# wav_player_861_mosfet_5x5.net
KiCad netlist of a schematic drawn in EAGLE
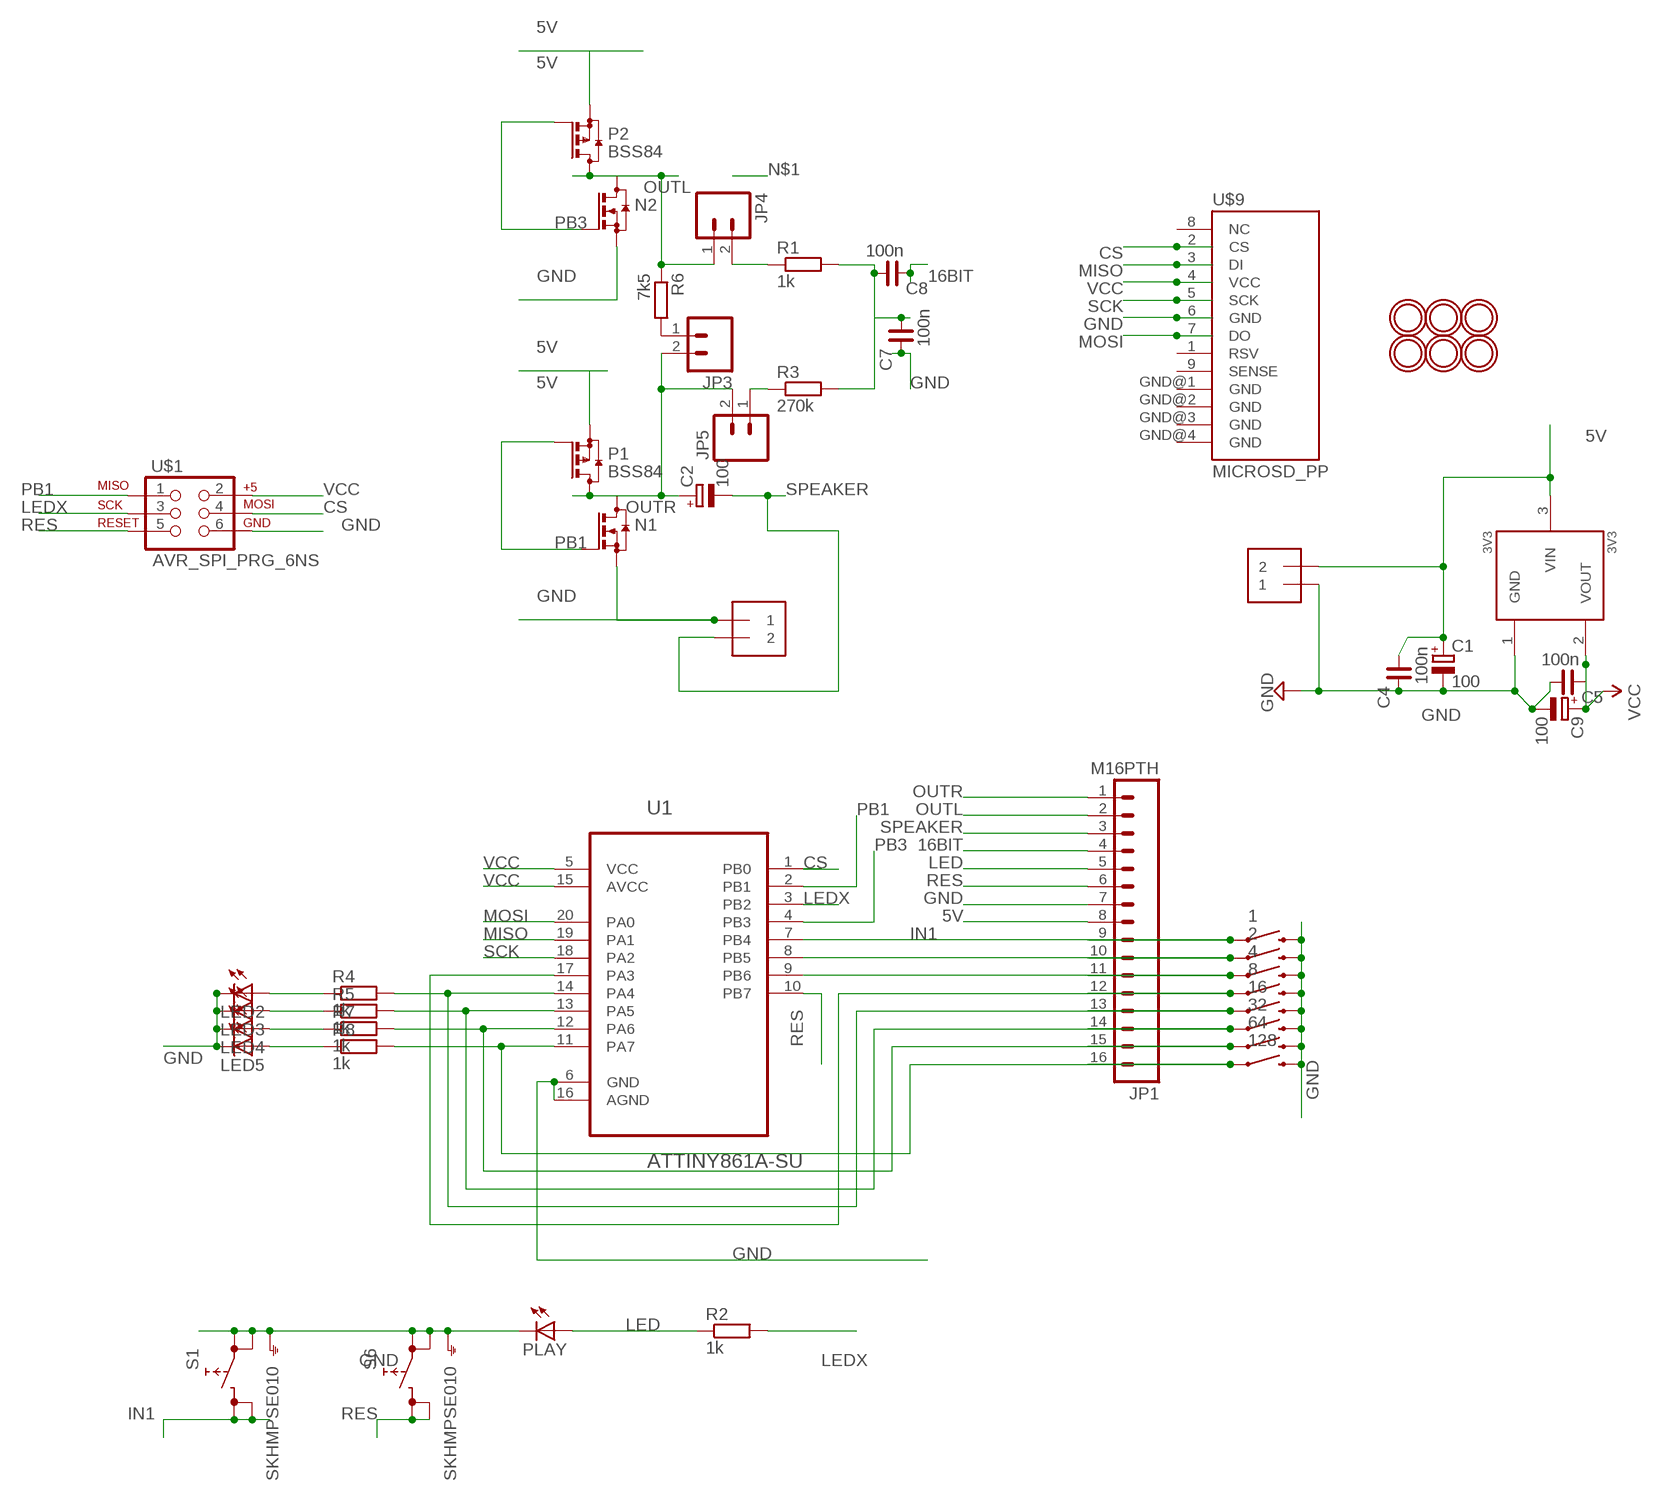
[diagram p0: schematic, sheet 1]

(export (version "E")
  (design (tool "Eeschema 10.0.6"))
  (components
    (comp (ref "1")
      (value "SWITCH-MOMENTARY-2-SMD-1101NE")
      (footprint "eagle-import:TACTILE-SWITCH-1101NE")
      (libsource (lib "eagle-import") (part "SWITCH-MOMENTARY-2-SMD-1101NE"))
    )
    (comp (ref "2")
      (value "SWITCH-MOMENTARY-2-SMD-1101NE")
      (footprint "eagle-import:TACTILE-SWITCH-1101NE")
      (libsource (lib "eagle-import") (part "SWITCH-MOMENTARY-2-SMD-1101NE"))
    )
    (comp (ref "3V3")
      (value "3V3")
      (footprint "eagle-import:SOT23")
      (libsource (lib "eagle-import") (part "MCP1700T"))
    )
    (comp (ref "4")
      (value "SWITCH-MOMENTARY-2-SMD-1101NE")
      (footprint "eagle-import:TACTILE-SWITCH-1101NE")
      (libsource (lib "eagle-import") (part "SWITCH-MOMENTARY-2-SMD-1101NE"))
    )
    (comp (ref "8")
      (value "SWITCH-MOMENTARY-2-SMD-1101NE")
      (footprint "eagle-import:TACTILE-SWITCH-1101NE")
      (libsource (lib "eagle-import") (part "SWITCH-MOMENTARY-2-SMD-1101NE"))
    )
    (comp (ref "16")
      (value "SWITCH-MOMENTARY-2-SMD-1101NE")
      (footprint "eagle-import:TACTILE-SWITCH-1101NE")
      (libsource (lib "eagle-import") (part "SWITCH-MOMENTARY-2-SMD-1101NE"))
    )
    (comp (ref "32")
      (value "SWITCH-MOMENTARY-2-SMD-1101NE")
      (footprint "eagle-import:TACTILE-SWITCH-1101NE")
      (libsource (lib "eagle-import") (part "SWITCH-MOMENTARY-2-SMD-1101NE"))
    )
    (comp (ref "64")
      (value "SWITCH-MOMENTARY-2-SMD-1101NE")
      (footprint "eagle-import:TACTILE-SWITCH-1101NE")
      (libsource (lib "eagle-import") (part "SWITCH-MOMENTARY-2-SMD-1101NE"))
    )
    (comp (ref "128")
      (value "SWITCH-MOMENTARY-2-SMD-1101NE")
      (footprint "eagle-import:TACTILE-SWITCH-1101NE")
      (libsource (lib "eagle-import") (part "SWITCH-MOMENTARY-2-SMD-1101NE"))
    )
    (comp (ref "C1")
      (value "100")
      (footprint "eagle-import:153CLV-0605")
      (libsource (lib "eagle-import") (part "CPOL-EU153CLV-0605"))
    )
    (comp (ref "C2")
      (value "100")
      (footprint "eagle-import:153CLV-0605")
      (libsource (lib "eagle-import") (part "CPOL-EU153CLV-0605"))
    )
    (comp (ref "C4")
      (value "100n")
      (footprint "eagle-import:C0603")
      (libsource (lib "eagle-import") (part "C_0603"))
    )
    (comp (ref "C5")
      (value "100n")
      (footprint "eagle-import:C0603")
      (libsource (lib "eagle-import") (part "C_0603"))
    )
    (comp (ref "C7")
      (value "100n")
      (footprint "eagle-import:C0603")
      (libsource (lib "eagle-import") (part "C_0603"))
    )
    (comp (ref "C8")
      (value "100n")
      (footprint "eagle-import:C0603")
      (libsource (lib "eagle-import") (part "C_0603"))
    )
    (comp (ref "C9")
      (value "100")
      (footprint "eagle-import:153CLV-0605")
      (libsource (lib "eagle-import") (part "CPOL-EU153CLV-0605"))
    )
    (comp (ref "J1")
      (value "1X2-3.5MM")
      (footprint "eagle-import:1X2-3.5MM")
      (libsource (lib "eagle-import") (part "1X2-3.5MM"))
    )
    (comp (ref "J2")
      (value "1X2-3.5MM")
      (footprint "eagle-import:1X2-3.5MM")
      (libsource (lib "eagle-import") (part "1X2-3.5MM"))
    )
    (comp (ref "JP1")
      (value "M16PTH")
      (footprint "eagle-import:1X16")
      (libsource (lib "eagle-import") (part "M16PTH"))
    )
    (comp (ref "JP3")
      (value "M02PTH")
      (footprint "eagle-import:1X02")
      (libsource (lib "eagle-import") (part "M02PTH"))
    )
    (comp (ref "JP4")
      (value "M02PTH")
      (footprint "eagle-import:1X02")
      (libsource (lib "eagle-import") (part "M02PTH"))
    )
    (comp (ref "JP5")
      (value "M02PTH")
      (footprint "eagle-import:1X02")
      (libsource (lib "eagle-import") (part "M02PTH"))
    )
    (comp (ref "LED2")
      (value "LED3MM")
      (footprint "eagle-import:LED3MM")
      (libsource (lib "eagle-import") (part "LED3MM"))
    )
    (comp (ref "LED3")
      (value "LED3MM")
      (footprint "eagle-import:LED3MM")
      (libsource (lib "eagle-import") (part "LED3MM"))
    )
    (comp (ref "LED4")
      (value "LED3MM")
      (footprint "eagle-import:LED3MM")
      (libsource (lib "eagle-import") (part "LED3MM"))
    )
    (comp (ref "LED5")
      (value "LED3MM")
      (footprint "eagle-import:LED3MM")
      (libsource (lib "eagle-import") (part "LED3MM"))
    )
    (comp (ref "N1")
      (value "BSS123")
      (footprint "eagle-import:SOT23")
      (libsource (lib "eagle-import") (part "BSS123"))
    )
    (comp (ref "N2")
      (value "BSS123")
      (footprint "eagle-import:SOT23")
      (libsource (lib "eagle-import") (part "BSS123"))
    )
    (comp (ref "P1")
      (value "BSS84")
      (footprint "eagle-import:SOT23")
      (libsource (lib "eagle-import") (part "BSS84"))
    )
    (comp (ref "P2")
      (value "BSS84")
      (footprint "eagle-import:SOT23")
      (libsource (lib "eagle-import") (part "BSS84"))
    )
    (comp (ref "PLAY")
      (value "LED3MM")
      (footprint "eagle-import:LED3MM")
      (libsource (lib "eagle-import") (part "LED3MM"))
    )
    (comp (ref "R1")
      (value "1k")
      (footprint "eagle-import:R0603")
      (libsource (lib "eagle-import") (part "R-EU_R0603"))
    )
    (comp (ref "R2")
      (value "1k")
      (footprint "eagle-import:R0603")
      (libsource (lib "eagle-import") (part "R-EU_R0603"))
    )
    (comp (ref "R3")
      (value "270k")
      (footprint "eagle-import:R0603")
      (libsource (lib "eagle-import") (part "R-EU_R0603"))
    )
    (comp (ref "R4")
      (value "1k")
      (footprint "eagle-import:R0603")
      (libsource (lib "eagle-import") (part "R-EU_R0603"))
    )
    (comp (ref "R5")
      (value "1k")
      (footprint "eagle-import:R0603")
      (libsource (lib "eagle-import") (part "R-EU_R0603"))
    )
    (comp (ref "R6")
      (value "7k5")
      (footprint "eagle-import:R0603")
      (libsource (lib "eagle-import") (part "R-EU_R0603"))
    )
    (comp (ref "R7")
      (value "1k")
      (footprint "eagle-import:R0603")
      (libsource (lib "eagle-import") (part "R-EU_R0603"))
    )
    (comp (ref "R8")
      (value "1k")
      (footprint "eagle-import:R0603")
      (libsource (lib "eagle-import") (part "R-EU_R0603"))
    )
    (comp (ref "S1")
      (value "SKHMPSE010")
      (footprint "eagle-import:SKHMPXE010")
      (libsource (lib "eagle-import") (part "SKHMPE010S"))
    )
    (comp (ref "S6")
      (value "SKHMPSE010")
      (footprint "eagle-import:SKHMPXE010")
      (libsource (lib "eagle-import") (part "SKHMPE010S"))
    )
    (comp (ref "U$1")
      (value "AVR_SPI_PRG_6NS")
      (footprint "eagle-import:2X3-NS")
      (libsource (lib "eagle-import") (part "AVR_SPI_PRG_6NS"))
    )
    (comp (ref "U$2")
      (value "MOUNTINGHOLE2.0")
      (footprint "eagle-import:MOUNTINGHOLE_2.0_PLATED")
      (libsource (lib "eagle-import") (part "MOUNTINGHOLE2.0"))
    )
    (comp (ref "U$3")
      (value "MOUNTINGHOLE2.0")
      (footprint "eagle-import:MOUNTINGHOLE_2.0_PLATED")
      (libsource (lib "eagle-import") (part "MOUNTINGHOLE2.0"))
    )
    (comp (ref "U$4")
      (value "MOUNTINGHOLE2.0")
      (footprint "eagle-import:MOUNTINGHOLE_2.0_PLATED")
      (libsource (lib "eagle-import") (part "MOUNTINGHOLE2.0"))
    )
    (comp (ref "U$5")
      (value "MOUNTINGHOLE2.0")
      (footprint "eagle-import:MOUNTINGHOLE_2.0_PLATED")
      (libsource (lib "eagle-import") (part "MOUNTINGHOLE2.0"))
    )
    (comp (ref "U$6")
      (value "MOUNTINGHOLE2.0")
      (footprint "eagle-import:MOUNTINGHOLE_2.0_PLATED")
      (libsource (lib "eagle-import") (part "MOUNTINGHOLE2.0"))
    )
    (comp (ref "U$7")
      (value "MOUNTINGHOLE2.0")
      (footprint "eagle-import:MOUNTINGHOLE_2.0_PLATED")
      (libsource (lib "eagle-import") (part "MOUNTINGHOLE2.0"))
    )
    (comp (ref "U$9")
      (value "MICROSD_PP")
      (footprint "eagle-import:MICROSD_PP")
      (libsource (lib "eagle-import") (part "MICROSD_PP"))
    )
    (comp (ref "U1")
      (value "ATTINY861A-SU")
      (footprint "eagle-import:SOIC127P1032X265-20N")
      (libsource (lib "eagle-import") (part "ATTINY861A-SU"))
    )
  )
  (nets
    (net (code "1") (name "/5V") (class "Default")
      (node (ref "3V3") (pin "3") (pinfunction "VIN_3") (pintype "bidirectional"))
      (node (ref "C1") (pin "+") (pinfunction "+_+") (pintype "passive"))
      (node (ref "C4") (pin "1") (pinfunction "1_1") (pintype "passive"))
      (node (ref "J2") (pin "2") (pinfunction "2_2") (pintype "passive"))
      (node (ref "JP1") (pin "8") (pinfunction "8_8") (pintype "passive"))
      (node (ref "P1") (pin "2") (pinfunction "S_2") (pintype "passive"))
      (node (ref "P2") (pin "2") (pinfunction "S_2") (pintype "passive"))
    )
    (net (code "2") (name "/16BIT") (class "Default")
      (node (ref "C8") (pin "2") (pinfunction "2_2") (pintype "passive"))
      (node (ref "JP1") (pin "4") (pinfunction "4_4") (pintype "passive"))
    )
    (net (code "3") (name "/CS") (class "Default")
      (node (ref "U$1") (pin "4") (pinfunction "4_4") (pintype "passive"))
      (node (ref "U$9") (pin "2") (pinfunction "CS_2") (pintype "bidirectional"))
      (node (ref "U1") (pin "1") (pinfunction "PB0_1") (pintype "bidirectional"))
    )
    (net (code "4") (name "/IN1") (class "Default")
      (node (ref "1") (pin "P$1") (pinfunction "1_P$1") (pintype "passive"))
      (node (ref "JP1") (pin "9") (pinfunction "9_9") (pintype "passive"))
      (node (ref "S1") (pin "3") (pinfunction "2.1_3") (pintype "passive"))
      (node (ref "S1") (pin "4") (pinfunction "2.2_4") (pintype "passive"))
      (node (ref "U1") (pin "7") (pinfunction "PB4_7") (pintype "bidirectional"))
    )
    (net (code "5") (name "/LED") (class "Default")
      (node (ref "JP1") (pin "5") (pinfunction "5_5") (pintype "passive"))
      (node (ref "PLAY") (pin "A") (pinfunction "A_A") (pintype "passive"))
      (node (ref "R2") (pin "1") (pinfunction "1_1") (pintype "passive"))
    )
    (net (code "6") (name "/LEDX") (class "Default")
      (node (ref "R2") (pin "2") (pinfunction "2_2") (pintype "passive"))
      (node (ref "U$1") (pin "3") (pinfunction "3_3") (pintype "passive"))
      (node (ref "U1") (pin "3") (pinfunction "PB2_3") (pintype "bidirectional"))
    )
    (net (code "7") (name "/MISO") (class "Default")
      (node (ref "U$9") (pin "3") (pinfunction "DI_3") (pintype "bidirectional"))
      (node (ref "U1") (pin "19") (pinfunction "PA1_19") (pintype "bidirectional"))
    )
    (net (code "8") (name "/MOSI") (class "Default")
      (node (ref "U$9") (pin "7") (pinfunction "DO_7") (pintype "bidirectional"))
      (node (ref "U1") (pin "20") (pinfunction "PA0_20") (pintype "bidirectional"))
    )
    (net (code "10") (name "/OUTL") (class "Default")
      (node (ref "JP1") (pin "2") (pinfunction "2_2") (pintype "passive"))
      (node (ref "JP4") (pin "1") (pinfunction "1_1") (pintype "passive"))
      (node (ref "N2") (pin "3") (pinfunction "D_3") (pintype "passive"))
      (node (ref "P2") (pin "3") (pinfunction "D_3") (pintype "passive"))
      (node (ref "R6") (pin "1") (pinfunction "1_1") (pintype "passive"))
    )
    (net (code "11") (name "/OUTR") (class "Default")
      (node (ref "C2") (pin "+") (pinfunction "+_+") (pintype "passive"))
      (node (ref "JP1") (pin "1") (pinfunction "1_1") (pintype "passive"))
      (node (ref "JP3") (pin "2") (pinfunction "2_2") (pintype "passive"))
      (node (ref "JP5") (pin "2") (pinfunction "2_2") (pintype "passive"))
      (node (ref "N1") (pin "3") (pinfunction "D_3") (pintype "passive"))
      (node (ref "P1") (pin "3") (pinfunction "D_3") (pintype "passive"))
    )
    (net (code "12") (name "/PB1") (class "Default")
      (node (ref "N1") (pin "1") (pinfunction "G_1") (pintype "passive"))
      (node (ref "P1") (pin "1") (pinfunction "G_1") (pintype "passive"))
      (node (ref "U$1") (pin "1") (pinfunction "1_1") (pintype "passive"))
      (node (ref "U1") (pin "2") (pinfunction "PB1_2") (pintype "bidirectional"))
    )
    (net (code "13") (name "/PB3") (class "Default")
      (node (ref "N2") (pin "1") (pinfunction "G_1") (pintype "passive"))
      (node (ref "P2") (pin "1") (pinfunction "G_1") (pintype "passive"))
      (node (ref "U1") (pin "4") (pinfunction "PB3_4") (pintype "bidirectional"))
    )
    (net (code "14") (name "/RES") (class "Default")
      (node (ref "JP1") (pin "6") (pinfunction "6_6") (pintype "passive"))
      (node (ref "S6") (pin "3") (pinfunction "2.1_3") (pintype "passive"))
      (node (ref "S6") (pin "4") (pinfunction "2.2_4") (pintype "passive"))
      (node (ref "U$1") (pin "5") (pinfunction "5_5") (pintype "passive"))
      (node (ref "U1") (pin "10") (pinfunction "PB7_10") (pintype "bidirectional"))
    )
    (net (code "15") (name "/SCK") (class "Default")
      (node (ref "U$9") (pin "5") (pinfunction "SCK_5") (pintype "bidirectional"))
      (node (ref "U1") (pin "18") (pinfunction "PA2_18") (pintype "bidirectional"))
    )
    (net (code "16") (name "/SPEAKER") (class "Default")
      (node (ref "C2") (pin "-") (pinfunction "-_-") (pintype "passive"))
      (node (ref "J1") (pin "2") (pinfunction "2_2") (pintype "passive"))
      (node (ref "JP1") (pin "3") (pinfunction "3_3") (pintype "passive"))
    )
    (net (code "17") (name "GND") (class "Default")
      (node (ref "1") (pin "P$2") (pinfunction "2_P$2") (pintype "passive"))
      (node (ref "128") (pin "P$2") (pinfunction "2_P$2") (pintype "passive"))
      (node (ref "16") (pin "P$2") (pinfunction "2_P$2") (pintype "passive"))
      (node (ref "2") (pin "P$2") (pinfunction "2_P$2") (pintype "passive"))
      (node (ref "32") (pin "P$2") (pinfunction "2_P$2") (pintype "passive"))
      (node (ref "3V3") (pin "1") (pinfunction "GND_1") (pintype "bidirectional"))
      (node (ref "4") (pin "P$2") (pinfunction "2_P$2") (pintype "passive"))
      (node (ref "64") (pin "P$2") (pinfunction "2_P$2") (pintype "passive"))
      (node (ref "8") (pin "P$2") (pinfunction "2_P$2") (pintype "passive"))
      (node (ref "C1") (pin "-") (pinfunction "-_-") (pintype "passive"))
      (node (ref "C4") (pin "2") (pinfunction "2_2") (pintype "passive"))
      (node (ref "C5") (pin "1") (pinfunction "1_1") (pintype "passive"))
      (node (ref "C7") (pin "2") (pinfunction "2_2") (pintype "passive"))
      (node (ref "C9") (pin "-") (pinfunction "-_-") (pintype "passive"))
      (node (ref "J1") (pin "1") (pinfunction "1_1") (pintype "passive"))
      (node (ref "J2") (pin "1") (pinfunction "1_1") (pintype "passive"))
      (node (ref "JP1") (pin "7") (pinfunction "7_7") (pintype "passive"))
      (node (ref "LED2") (pin "K") (pinfunction "C_K") (pintype "passive"))
      (node (ref "LED3") (pin "K") (pinfunction "C_K") (pintype "passive"))
      (node (ref "LED4") (pin "K") (pinfunction "C_K") (pintype "passive"))
      (node (ref "LED5") (pin "K") (pinfunction "C_K") (pintype "passive"))
      (node (ref "N1") (pin "2") (pinfunction "S_2") (pintype "passive"))
      (node (ref "N2") (pin "2") (pinfunction "S_2") (pintype "passive"))
      (node (ref "PLAY") (pin "K") (pinfunction "C_K") (pintype "passive"))
      (node (ref "S1") (pin "1") (pinfunction "1.1_1") (pintype "passive"))
      (node (ref "S1") (pin "2") (pinfunction "1.2_2") (pintype "passive"))
      (node (ref "S1") (pin "5") (pinfunction "SH_5") (pintype "passive"))
      (node (ref "S6") (pin "1") (pinfunction "1.1_1") (pintype "passive"))
      (node (ref "S6") (pin "2") (pinfunction "1.2_2") (pintype "passive"))
      (node (ref "S6") (pin "5") (pinfunction "SH_5") (pintype "passive"))
      (node (ref "U$1") (pin "6") (pinfunction "6_6") (pintype "passive"))
      (node (ref "U$9") (pin "6") (pinfunction "GND_6") (pintype "bidirectional"))
      (node (ref "U1") (pin "16") (pinfunction "AGND_16") (pintype "passive"))
      (node (ref "U1") (pin "6") (pinfunction "GND_6") (pintype "passive"))
    )
    (net (code "18") (name "Net-(2-1)") (class "Default")
      (node (ref "2") (pin "P$1") (pinfunction "1_P$1") (pintype "passive"))
      (node (ref "JP1") (pin "10") (pinfunction "10_10") (pintype "passive"))
      (node (ref "U1") (pin "8") (pinfunction "PB5_8") (pintype "bidirectional"))
    )
    (net (code "19") (name "Net-(4-1)") (class "Default")
      (node (ref "4") (pin "P$1") (pinfunction "1_P$1") (pintype "passive"))
      (node (ref "JP1") (pin "11") (pinfunction "11_11") (pintype "passive"))
      (node (ref "U1") (pin "9") (pinfunction "PB6_9") (pintype "bidirectional"))
    )
    (net (code "20") (name "Net-(8-1)") (class "Default")
      (node (ref "8") (pin "P$1") (pinfunction "1_P$1") (pintype "passive"))
      (node (ref "JP1") (pin "12") (pinfunction "12_12") (pintype "passive"))
      (node (ref "U1") (pin "17") (pinfunction "PA3_17") (pintype "bidirectional"))
    )
    (net (code "21") (name "Net-(16-1)") (class "Default")
      (node (ref "16") (pin "P$1") (pinfunction "1_P$1") (pintype "passive"))
      (node (ref "JP1") (pin "13") (pinfunction "13_13") (pintype "passive"))
      (node (ref "R4") (pin "2") (pinfunction "2_2") (pintype "passive"))
      (node (ref "U1") (pin "14") (pinfunction "PA4_14") (pintype "bidirectional"))
    )
    (net (code "22") (name "Net-(32-1)") (class "Default")
      (node (ref "32") (pin "P$1") (pinfunction "1_P$1") (pintype "passive"))
      (node (ref "JP1") (pin "14") (pinfunction "14_14") (pintype "passive"))
      (node (ref "R5") (pin "2") (pinfunction "2_2") (pintype "passive"))
      (node (ref "U1") (pin "13") (pinfunction "PA5_13") (pintype "bidirectional"))
    )
    (net (code "23") (name "Net-(64-1)") (class "Default")
      (node (ref "64") (pin "P$1") (pinfunction "1_P$1") (pintype "passive"))
      (node (ref "JP1") (pin "15") (pinfunction "15_15") (pintype "passive"))
      (node (ref "R7") (pin "2") (pinfunction "2_2") (pintype "passive"))
      (node (ref "U1") (pin "12") (pinfunction "PA6_12") (pintype "bidirectional"))
    )
    (net (code "24") (name "Net-(128-1)") (class "Default")
      (node (ref "128") (pin "P$1") (pinfunction "1_P$1") (pintype "passive"))
      (node (ref "JP1") (pin "16") (pinfunction "16_16") (pintype "passive"))
      (node (ref "R8") (pin "2") (pinfunction "2_2") (pintype "passive"))
      (node (ref "U1") (pin "11") (pinfunction "PA7_11") (pintype "bidirectional"))
    )
    (net (code "25") (name "Net-(C7-Pad1)") (class "Default")
      (node (ref "C7") (pin "1") (pinfunction "1_1") (pintype "passive"))
      (node (ref "C8") (pin "1") (pinfunction "1_1") (pintype "passive"))
      (node (ref "R1") (pin "2") (pinfunction "2_2") (pintype "passive"))
      (node (ref "R3") (pin "2") (pinfunction "2_2") (pintype "passive"))
    )
    (net (code "26") (name "Net-(JP3-Pad1)") (class "Default")
      (node (ref "JP3") (pin "1") (pinfunction "1_1") (pintype "passive"))
      (node (ref "R6") (pin "2") (pinfunction "2_2") (pintype "passive"))
    )
    (net (code "27") (name "Net-(JP4-Pad2)") (class "Default")
      (node (ref "JP4") (pin "2") (pinfunction "2_2") (pintype "passive"))
      (node (ref "R1") (pin "1") (pinfunction "1_1") (pintype "passive"))
    )
    (net (code "28") (name "Net-(JP5-Pad1)") (class "Default")
      (node (ref "JP5") (pin "1") (pinfunction "1_1") (pintype "passive"))
      (node (ref "R3") (pin "1") (pinfunction "1_1") (pintype "passive"))
    )
    (net (code "29") (name "Net-(LED2-PadA)") (class "Default")
      (node (ref "LED2") (pin "A") (pinfunction "A_A") (pintype "passive"))
      (node (ref "R4") (pin "1") (pinfunction "1_1") (pintype "passive"))
    )
    (net (code "30") (name "Net-(LED3-PadA)") (class "Default")
      (node (ref "LED3") (pin "A") (pinfunction "A_A") (pintype "passive"))
      (node (ref "R5") (pin "1") (pinfunction "1_1") (pintype "passive"))
    )
    (net (code "31") (name "Net-(LED4-PadA)") (class "Default")
      (node (ref "LED4") (pin "A") (pinfunction "A_A") (pintype "passive"))
      (node (ref "R7") (pin "1") (pinfunction "1_1") (pintype "passive"))
    )
    (net (code "32") (name "Net-(LED5-PadA)") (class "Default")
      (node (ref "LED5") (pin "A") (pinfunction "A_A") (pintype "passive"))
      (node (ref "R8") (pin "1") (pinfunction "1_1") (pintype "passive"))
    )
    (net (code "33") (name "VCC") (class "Default")
      (node (ref "3V3") (pin "2") (pinfunction "VOUT_2") (pintype "bidirectional"))
      (node (ref "C5") (pin "2") (pinfunction "2_2") (pintype "passive"))
      (node (ref "C9") (pin "+") (pinfunction "+_+") (pintype "passive"))
      (node (ref "U$1") (pin "2") (pinfunction "2_2") (pintype "passive"))
      (node (ref "U$9") (pin "4") (pinfunction "VCC_4") (pintype "bidirectional"))
      (node (ref "U1") (pin "15") (pinfunction "AVCC_15") (pintype "power_in"))
      (node (ref "U1") (pin "5") (pinfunction "VCC_5") (pintype "power_in"))
    )
    (net (code "34") (name "unconnected-(U$9-GND-PadGND@1)") (class "Default")
      (node (ref "U$9") (pin "GND@1") (pinfunction "GND_GND@1") (pintype "bidirectional"))
    )
    (net (code "35") (name "unconnected-(U$9-GND-PadGND@2)") (class "Default")
      (node (ref "U$9") (pin "GND@2") (pinfunction "GND_GND@2") (pintype "bidirectional"))
    )
    (net (code "36") (name "unconnected-(U$9-GND-PadGND@3)") (class "Default")
      (node (ref "U$9") (pin "GND@3") (pinfunction "GND_GND@3") (pintype "bidirectional"))
    )
    (net (code "37") (name "unconnected-(U$9-GND-PadGND@4)") (class "Default")
      (node (ref "U$9") (pin "GND@4") (pinfunction "GND_GND@4") (pintype "bidirectional"))
    )
    (net (code "38") (name "unconnected-(U$9-NC-Pad8)") (class "Default")
      (node (ref "U$9") (pin "8") (pinfunction "NC_8") (pintype "bidirectional"))
    )
    (net (code "39") (name "unconnected-(U$9-RSV-Pad1)") (class "Default")
      (node (ref "U$9") (pin "1") (pinfunction "RSV_1") (pintype "bidirectional"))
    )
    (net (code "40") (name "unconnected-(U$9-SENSE-Pad9)") (class "Default")
      (node (ref "U$9") (pin "9") (pinfunction "SENSE_9") (pintype "bidirectional"))
    )
  )
)
